# Connectors.net
KiCad netlist of a schematic drawn in Altium Designer
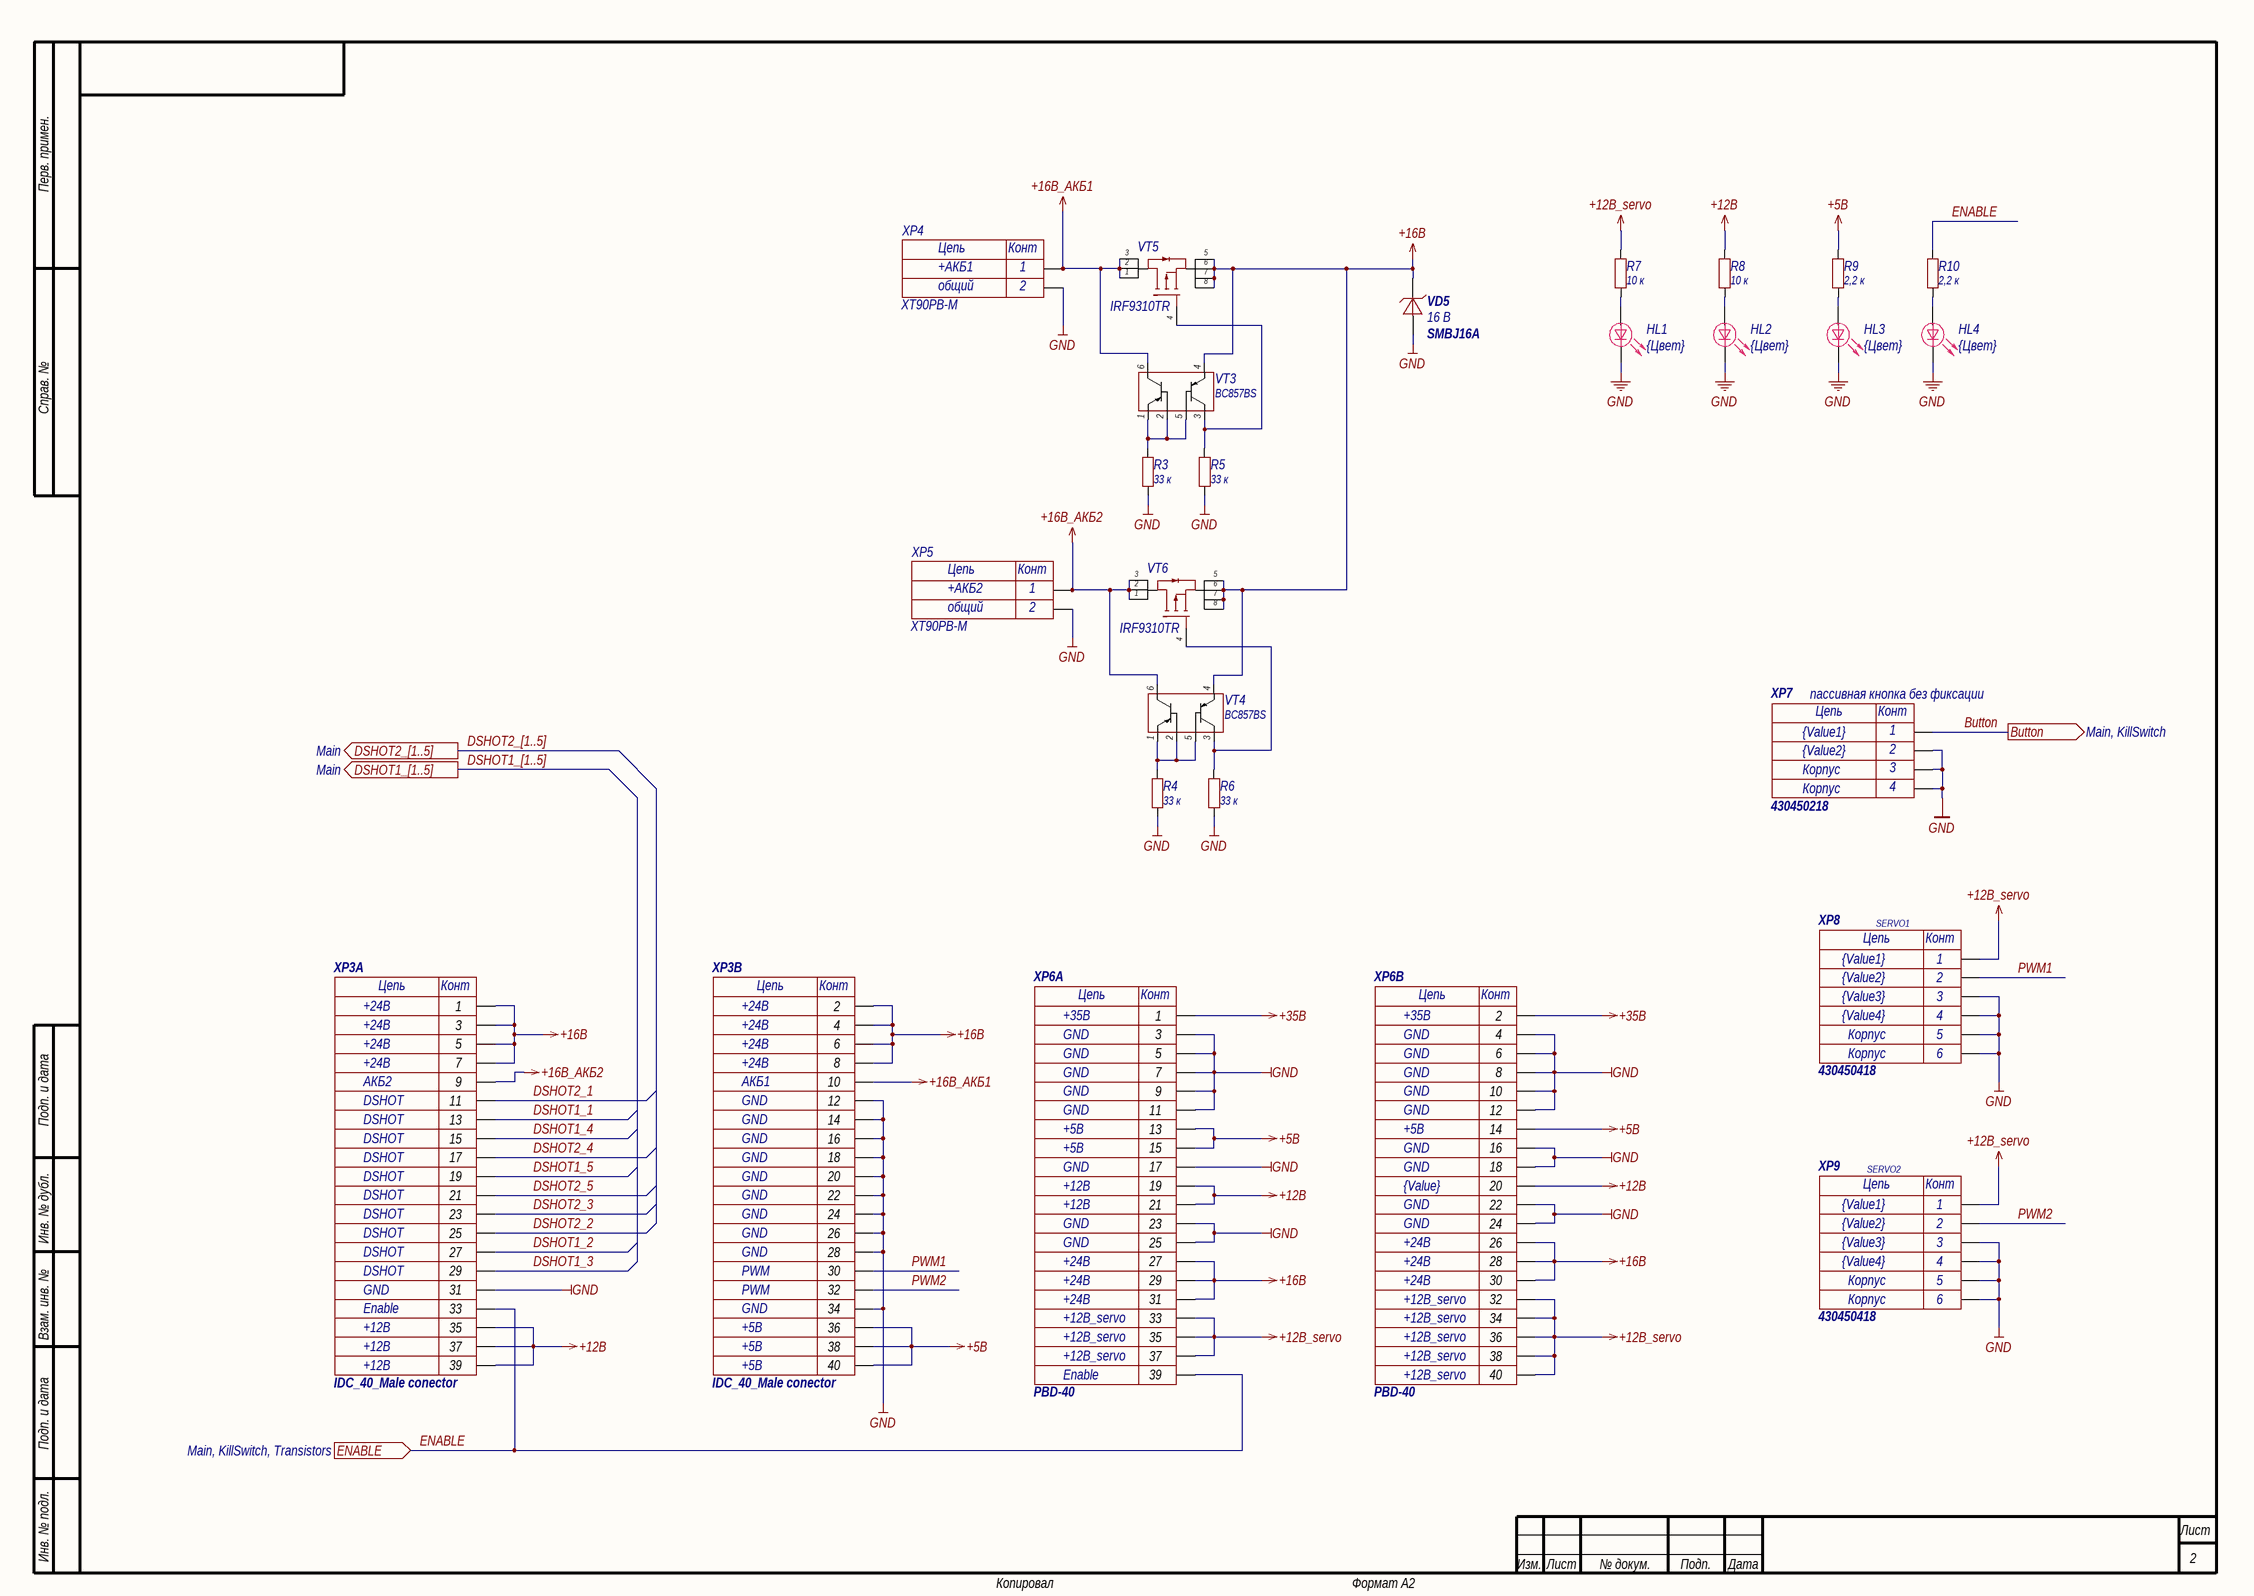
[diagram p0: Connectors.SchDoc]

(export (version "E")
  (design (tool "Eeschema 10.0.6"))
  (components
    (comp (ref "HL1")
      (value "LED")
      (footprint "0805D")
      (description "Светодиод")
      (fields (field (name "COLOR") "{Цвет}"))
      (libsource (lib "Hydrolib") (part "LED"))
    )
    (comp (ref "HL2")
      (value "LED")
      (footprint "0805D")
      (description "Светодиод")
      (fields (field (name "COLOR") "{Цвет}"))
      (libsource (lib "Hydrolib") (part "LED"))
    )
    (comp (ref "HL3")
      (value "LED")
      (footprint "0805D")
      (description "Светодиод")
      (fields (field (name "COLOR") "{Цвет}"))
      (libsource (lib "Hydrolib") (part "LED"))
    )
    (comp (ref "HL4")
      (value "LED")
      (footprint "0805D")
      (description "Светодиод")
      (fields (field (name "COLOR") "{Цвет}"))
      (libsource (lib "Hydrolib") (part "LED"))
    )
    (comp (ref "R3")
      (value "33 к")
      (footprint "0603R")
      (description "Резистор номиналом 33 кОм и точностью 1%")
      (fields (field (name "PART NUMBER") "Resistor_33k_1_0603") (field (name "TOLERANCE") "1%"))
      (libsource (lib "Hydrolib") (part "Resistor"))
    )
    (comp (ref "R4")
      (value "33 к")
      (footprint "0603R")
      (description "Резистор номиналом 33 кОм и точностью 1%")
      (fields (field (name "PART NUMBER") "Resistor_33k_1_0603") (field (name "TOLERANCE") "1%"))
      (libsource (lib "Hydrolib") (part "Resistor"))
    )
    (comp (ref "R5")
      (value "33 к")
      (footprint "0603R")
      (description "Резистор номиналом 33 кОм и точностью 1%")
      (fields (field (name "PART NUMBER") "Resistor_33k_1_0603") (field (name "TOLERANCE") "1%"))
      (libsource (lib "Hydrolib") (part "Resistor"))
    )
    (comp (ref "R6")
      (value "33 к")
      (footprint "0603R")
      (description "Резистор номиналом 33 кОм и точностью 1%")
      (fields (field (name "PART NUMBER") "Resistor_33k_1_0603") (field (name "TOLERANCE") "1%"))
      (libsource (lib "Hydrolib") (part "Resistor"))
    )
    (comp (ref "R7")
      (value "10 к")
      (footprint "0603R")
      (description "Резистор номиналом 10 кОм и точностью 1%")
      (fields (field (name "PART NUMBER") "Resistor_10k_1_0603") (field (name "TOLERANCE") "1%"))
      (libsource (lib "Hydrolib") (part "Resistor"))
    )
    (comp (ref "R8")
      (value "10 к")
      (footprint "0603R")
      (description "Резистор номиналом 10 кОм и точностью 1%")
      (fields (field (name "PART NUMBER") "Resistor_10k_1_0603") (field (name "TOLERANCE") "1%"))
      (libsource (lib "Hydrolib") (part "Resistor"))
    )
    (comp (ref "R9")
      (value "2,2 к")
      (footprint "0603R")
      (description "Резистор номиналом 2,2 кОм и точностью 1%")
      (fields (field (name "PART NUMBER") "Resistor_2.2k_1_0603") (field (name "TOLERANCE") "1%"))
      (libsource (lib "Hydrolib") (part "Resistor"))
    )
    (comp (ref "R10")
      (value "2,2 к")
      (footprint "0603R")
      (description "Резистор номиналом 2,2 кОм и точностью 1%")
      (fields (field (name "PART NUMBER") "Resistor_2.2k_1_0603") (field (name "TOLERANCE") "1%"))
      (libsource (lib "Hydrolib") (part "Resistor"))
    )
    (comp (ref "VD5")
      (value "SMBJ16A")
      (footprint "SMB")
      (description "Защитный диод на 16 В, рассеиваемая мощность 600 Вт")
      (fields (field (name "ALTIUM_VALUE") "16 В") (field (name "АВТОР") "glebmih"))
      (libsource (lib "Hydrolib") (part "TVS_1_1dir"))
    )
    (comp (ref "VT3")
      (value "BC857BS")
      (footprint "SOT-363_35um")
      (description "Сборка из биполярных транзисторов, 2 pnp, 45 В,  0.1А")
      (fields (field (name "АВТОР") "glebmih"))
      (libsource (lib "Hydrolib") (part "2pnp"))
    )
    (comp (ref "VT4")
      (value "BC857BS")
      (footprint "SOT-363_35um")
      (description "Сборка из биполярных транзисторов, 2 pnp, 45 В,  0.1А")
      (fields (field (name "АВТОР") "glebmih"))
      (libsource (lib "Hydrolib") (part "2pnp"))
    )
    (comp (ref "VT5")
      (value "IRF9310TR")
      (footprint "SOIC-8")
      (description "P-канальный MOSFET, 30 В, 20 А")
      (fields (field (name "АВТОР") "glebmih"))
      (libsource (lib "Hydrolib") (part "MOSFET_P-channel_8pin"))
    )
    (comp (ref "VT6")
      (value "IRF9310TR")
      (footprint "SOIC-8")
      (description "P-канальный MOSFET, 30 В, 20 А")
      (fields (field (name "АВТОР") "glebmih"))
      (libsource (lib "Hydrolib") (part "MOSFET_P-channel_8pin"))
    )
    (comp (ref "XP3")
      (value "IDC_40_Male conector")
      (footprint "IDC_40_Male conector")
      (description "IDC 40-пиновый разъём прямая вилка")
      (fields
        (field (name "VALUE17") "Enable")
        (field (name "VALUE20") "+12В")
        (field (name "VALUE19") "+12В")
        (field (name "VALUE18") "+12В")
        (field (name "VALUE16") "GND")
        (field (name "VALUE15") "DSHOT")
        (field (name "VALUE14") "DSHOT")
        (field (name "VALUE13") "DSHOT")
        (field (name "VALUE12") "DSHOT")
        (field (name "VALUE11") "DSHOT")
        (field (name "VALUE10") "DSHOT")
        (field (name "VALUE9") "DSHOT")
        (field (name "VALUE8") "DSHOT")
        (field (name "VALUE7") "DSHOT")
        (field (name "VALUE6") "DSHOT")
        (field (name "VALUE5") "АКБ2")
        (field (name "VALUE1") "+24В")
        (field (name "VALUE1_1") "+24В")
        (field (name "VALUE1_2") "+24В")
        (field (name "VALUE1_3") "+24В")
        (field (name "VALUE4") "+24В")
        (field (name "VALUE3") "+24В")
        (field (name "VALUE2") "+24В")
      )
      (libsource (lib "Hydrolib") (part "Conn_40pin_double"))
    )
    (comp (ref "XP4")
      (value "XT90PB-M")
      (footprint "XT90PB-M")
      (description "90 А (60 продолжительно), 2 контакта, прямой отец")
      (fields (field (name "VALUE2") "общий") (field (name "VALUE1") "+АКБ1"))
      (libsource (lib "Hydrolib") (part "Polar_Conn"))
    )
    (comp (ref "XP5")
      (value "XT90PB-M")
      (footprint "XT90PB-M")
      (description "90 А (60 продолжительно), 2 контакта, прямой отец")
      (fields (field (name "VALUE2") "общий") (field (name "VALUE1") "+АКБ2"))
      (libsource (lib "Hydrolib") (part "Polar_Conn"))
    )
    (comp (ref "XP6")
      (value "PBD-40")
      (footprint "DCDC_SAUVC26:DCDC_SAUVC26")
      (description "Плата DCDC преобрахователей")
      (fields
        (field (name "VALUE17") "+12В_servo")
        (field (name "VALUE20") "Enable")
        (field (name "VALUE19") "+12В_servo")
        (field (name "VALUE18") "+12В_servo")
        (field (name "VALUE16") "+24В")
        (field (name "VALUE15") "+24В")
        (field (name "VALUE14") "+24В")
        (field (name "VALUE13") "GND")
        (field (name "VALUE12") "GND")
        (field (name "VALUE11") "+12В")
        (field (name "VALUE10") "+12В")
        (field (name "VALUE9") "GND")
        (field (name "VALUE8") "+5В")
        (field (name "VALUE7") "+5В")
        (field (name "VALUE6") "GND")
        (field (name "VALUE5") "GND")
        (field (name "VALUE4") "GND")
        (field (name "VALUE3") "GND")
        (field (name "VALUE2") "GND")
        (field (name "VALUE1") "+35В")
      )
      (libsource (lib "DCDC_SAUVC26") (part "DCDC_SAUVC26"))
    )
    (comp (ref "XP7")
      (value "430450218")
      (footprint "Molex_430450218")
      (fields
        (field (name "VALUE3") "Корпус")
        (field (name "VALUE2") "{Value2}")
        (field (name "VALUE4") "Корпус")
        (field (name "VALUE1") "{Value1}")
        (field (name "PART NUMBER") "Molex_430450218")
      )
      (libsource (lib "Hydrolib") (part "Molex_430450218"))
    )
    (comp (ref "XP8")
      (value "430450418")
      (footprint "MOLEX_430450418")
      (description "Разъем типа провод-плата, 3 мм, 4 контакт(-ов), Штыревой Разъем, для поверностного монтажа")
      (fields
        (field (name "VALUE1") "{Value1}")
        (field (name "VALUE2") "{Value2}")
        (field (name "VALUE3") "{Value3}")
        (field (name "VALUE4") "{Value4}")
        (field (name "PART NUMBER") "Molex_430450418")
      )
      (libsource (lib "Hydrolib") (part "Molex_430450415"))
    )
    (comp (ref "XP9")
      (value "430450418")
      (footprint "MOLEX_430450418")
      (description "Разъем типа провод-плата, 3 мм, 4 контакт(-ов), Штыревой Разъем, для поверностного монтажа")
      (fields
        (field (name "VALUE1") "{Value1}")
        (field (name "VALUE2") "{Value2}")
        (field (name "VALUE3") "{Value3}")
        (field (name "VALUE4") "{Value4}")
        (field (name "PART NUMBER") "Molex_430450418")
      )
      (libsource (lib "Hydrolib") (part "Molex_430450415"))
    )
  )
  (nets
    (net (code "1") (name "+5В") (class "Default")
      (node (ref "R9") (pin "2") (pinfunction "2_2") (pintype "passive"))
      (node (ref "XP3") (pin "36") (pinfunction "36_36") (pintype "passive"))
      (node (ref "XP3") (pin "38") (pinfunction "38_38") (pintype "passive"))
      (node (ref "XP3") (pin "40") (pinfunction "40_40") (pintype "passive"))
      (node (ref "XP6") (pin "13") (pinfunction "13_13") (pintype "passive"))
      (node (ref "XP6") (pin "14") (pinfunction "14_14") (pintype "passive"))
      (node (ref "XP6") (pin "15") (pinfunction "15_15") (pintype "passive"))
    )
    (net (code "2") (name "+12В") (class "Default")
      (node (ref "R8") (pin "2") (pinfunction "2_2") (pintype "passive"))
      (node (ref "XP3") (pin "35") (pinfunction "35_35") (pintype "passive"))
      (node (ref "XP3") (pin "37") (pinfunction "37_37") (pintype "passive"))
      (node (ref "XP3") (pin "39") (pinfunction "39_39") (pintype "passive"))
      (node (ref "XP6") (pin "19") (pinfunction "19_19") (pintype "passive"))
      (node (ref "XP6") (pin "20") (pinfunction "20_20") (pintype "passive"))
      (node (ref "XP6") (pin "21") (pinfunction "21_21") (pintype "passive"))
    )
    (net (code "3") (name "+12В_servo") (class "Default")
      (node (ref "R7") (pin "2") (pinfunction "2_2") (pintype "passive"))
      (node (ref "XP6") (pin "32") (pinfunction "32_32") (pintype "passive"))
      (node (ref "XP6") (pin "33") (pinfunction "33_33") (pintype "passive"))
      (node (ref "XP6") (pin "34") (pinfunction "34_34") (pintype "passive"))
      (node (ref "XP6") (pin "35") (pinfunction "35_35") (pintype "passive"))
      (node (ref "XP6") (pin "36") (pinfunction "36_36") (pintype "passive"))
      (node (ref "XP6") (pin "37") (pinfunction "37_37") (pintype "passive"))
      (node (ref "XP6") (pin "38") (pinfunction "38_38") (pintype "passive"))
      (node (ref "XP6") (pin "40") (pinfunction "40_40") (pintype "passive"))
      (node (ref "XP8") (pin "1") (pinfunction "1_1") (pintype "passive"))
      (node (ref "XP9") (pin "1") (pinfunction "1_1") (pintype "passive"))
    )
    (net (code "4") (name "+16В") (class "Default")
      (node (ref "VD5") (pin "2") (pinfunction "2_2") (pintype "passive"))
      (node (ref "VT3") (pin "4") (pinfunction "4_4") (pintype "passive"))
      (node (ref "VT4") (pin "4") (pinfunction "4_4") (pintype "passive"))
      (node (ref "VT5") (pin "5") (pinfunction "5_5") (pintype "passive"))
      (node (ref "VT5") (pin "6") (pinfunction "6_6") (pintype "passive"))
      (node (ref "VT5") (pin "7") (pinfunction "7_7") (pintype "passive"))
      (node (ref "VT5") (pin "8") (pinfunction "8_8") (pintype "passive"))
      (node (ref "VT6") (pin "5") (pinfunction "5_5") (pintype "passive"))
      (node (ref "VT6") (pin "6") (pinfunction "6_6") (pintype "passive"))
      (node (ref "VT6") (pin "7") (pinfunction "7_7") (pintype "passive"))
      (node (ref "VT6") (pin "8") (pinfunction "8_8") (pintype "passive"))
      (node (ref "XP3") (pin "1") (pinfunction "1_1") (pintype "passive"))
      (node (ref "XP3") (pin "2") (pinfunction "2_2") (pintype "passive"))
      (node (ref "XP3") (pin "3") (pinfunction "3_3") (pintype "passive"))
      (node (ref "XP3") (pin "4") (pinfunction "4_4") (pintype "passive"))
      (node (ref "XP3") (pin "5") (pinfunction "5_5") (pintype "passive"))
      (node (ref "XP3") (pin "6") (pinfunction "6_6") (pintype "passive"))
      (node (ref "XP3") (pin "7") (pinfunction "7_7") (pintype "passive"))
      (node (ref "XP3") (pin "8") (pinfunction "8_8") (pintype "passive"))
      (node (ref "XP6") (pin "26") (pinfunction "26_26") (pintype "passive"))
      (node (ref "XP6") (pin "27") (pinfunction "27_27") (pintype "passive"))
      (node (ref "XP6") (pin "28") (pinfunction "28_28") (pintype "passive"))
      (node (ref "XP6") (pin "29") (pinfunction "29_29") (pintype "passive"))
      (node (ref "XP6") (pin "30") (pinfunction "30_30") (pintype "passive"))
      (node (ref "XP6") (pin "31") (pinfunction "31_31") (pintype "passive"))
    )
    (net (code "5") (name "+16В_АКБ1") (class "Default")
      (node (ref "VT3") (pin "6") (pinfunction "6_6") (pintype "passive"))
      (node (ref "VT5") (pin "1") (pinfunction "1_1") (pintype "passive"))
      (node (ref "VT5") (pin "2") (pinfunction "2_2") (pintype "passive"))
      (node (ref "VT5") (pin "3") (pinfunction "3_3") (pintype "passive"))
      (node (ref "XP3") (pin "10") (pinfunction "10_10") (pintype "passive"))
      (node (ref "XP4") (pin "P") (pinfunction "P_P") (pintype "passive"))
    )
    (net (code "6") (name "+16В_АКБ2") (class "Default")
      (node (ref "VT4") (pin "6") (pinfunction "6_6") (pintype "passive"))
      (node (ref "VT6") (pin "1") (pinfunction "1_1") (pintype "passive"))
      (node (ref "VT6") (pin "2") (pinfunction "2_2") (pintype "passive"))
      (node (ref "VT6") (pin "3") (pinfunction "3_3") (pintype "passive"))
      (node (ref "XP3") (pin "9") (pinfunction "9_9") (pintype "passive"))
      (node (ref "XP5") (pin "P") (pinfunction "P_P") (pintype "passive"))
    )
    (net (code "7") (name "+35В") (class "Default")
      (node (ref "XP6") (pin "1") (pinfunction "1_1") (pintype "passive"))
      (node (ref "XP6") (pin "2") (pinfunction "2_2") (pintype "passive"))
    )
    (net (code "8") (name "/Button") (class "Default")
      (node (ref "XP7") (pin "1") (pinfunction "1_1") (pintype "passive"))
    )
    (net (code "9") (name "/DSHOT1_1") (class "Default")
      (node (ref "XP3") (pin "13") (pinfunction "13_13") (pintype "passive"))
    )
    (net (code "10") (name "/DSHOT1_2") (class "Default")
      (node (ref "XP3") (pin "27") (pinfunction "27_27") (pintype "passive"))
    )
    (net (code "11") (name "/DSHOT1_3") (class "Default")
      (node (ref "XP3") (pin "29") (pinfunction "29_29") (pintype "passive"))
    )
    (net (code "12") (name "/DSHOT1_4") (class "Default")
      (node (ref "XP3") (pin "15") (pinfunction "15_15") (pintype "passive"))
    )
    (net (code "13") (name "/DSHOT1_5") (class "Default")
      (node (ref "XP3") (pin "19") (pinfunction "19_19") (pintype "passive"))
    )
    (net (code "15") (name "/DSHOT2_1") (class "Default")
      (node (ref "XP3") (pin "11") (pinfunction "11_11") (pintype "passive"))
    )
    (net (code "16") (name "/DSHOT2_2") (class "Default")
      (node (ref "XP3") (pin "25") (pinfunction "25_25") (pintype "passive"))
    )
    (net (code "17") (name "/DSHOT2_3") (class "Default")
      (node (ref "XP3") (pin "23") (pinfunction "23_23") (pintype "passive"))
    )
    (net (code "18") (name "/DSHOT2_4") (class "Default")
      (node (ref "XP3") (pin "17") (pinfunction "17_17") (pintype "passive"))
    )
    (net (code "19") (name "/DSHOT2_5") (class "Default")
      (node (ref "XP3") (pin "21") (pinfunction "21_21") (pintype "passive"))
    )
    (net (code "21") (name "/ENABLE") (class "Default")
      (node (ref "R10") (pin "2") (pinfunction "2_2") (pintype "passive"))
      (node (ref "XP3") (pin "33") (pinfunction "33_33") (pintype "passive"))
      (node (ref "XP6") (pin "39") (pinfunction "39_39") (pintype "passive"))
    )
    (net (code "22") (name "/PWM1") (class "Default")
      (node (ref "XP3") (pin "30") (pinfunction "30_30") (pintype "passive"))
      (node (ref "XP8") (pin "2") (pinfunction "2_2") (pintype "passive"))
    )
    (net (code "23") (name "/PWM2") (class "Default")
      (node (ref "XP3") (pin "32") (pinfunction "32_32") (pintype "passive"))
      (node (ref "XP9") (pin "2") (pinfunction "2_2") (pintype "passive"))
    )
    (net (code "24") (name "GND") (class "Default")
      (node (ref "HL1") (pin "2") (pinfunction "2_2") (pintype "passive"))
      (node (ref "HL2") (pin "2") (pinfunction "2_2") (pintype "passive"))
      (node (ref "HL3") (pin "2") (pinfunction "2_2") (pintype "passive"))
      (node (ref "HL4") (pin "2") (pinfunction "2_2") (pintype "passive"))
      (node (ref "R3") (pin "1") (pinfunction "1_1") (pintype "passive"))
      (node (ref "R4") (pin "1") (pinfunction "1_1") (pintype "passive"))
      (node (ref "R5") (pin "1") (pinfunction "1_1") (pintype "passive"))
      (node (ref "R6") (pin "1") (pinfunction "1_1") (pintype "passive"))
      (node (ref "VD5") (pin "1") (pinfunction "1_1") (pintype "passive"))
      (node (ref "XP3") (pin "12") (pinfunction "12_12") (pintype "passive"))
      (node (ref "XP3") (pin "14") (pinfunction "14_14") (pintype "passive"))
      (node (ref "XP3") (pin "16") (pinfunction "16_16") (pintype "passive"))
      (node (ref "XP3") (pin "18") (pinfunction "18_18") (pintype "passive"))
      (node (ref "XP3") (pin "20") (pinfunction "20_20") (pintype "passive"))
      (node (ref "XP3") (pin "22") (pinfunction "22_22") (pintype "passive"))
      (node (ref "XP3") (pin "24") (pinfunction "24_24") (pintype "passive"))
      (node (ref "XP3") (pin "26") (pinfunction "26_26") (pintype "passive"))
      (node (ref "XP3") (pin "28") (pinfunction "28_28") (pintype "passive"))
      (node (ref "XP3") (pin "31") (pinfunction "31_31") (pintype "passive"))
      (node (ref "XP3") (pin "34") (pinfunction "34_34") (pintype "passive"))
      (node (ref "XP4") (pin "N") (pinfunction "N_N") (pintype "passive"))
      (node (ref "XP5") (pin "N") (pinfunction "N_N") (pintype "passive"))
      (node (ref "XP6") (pin "10") (pinfunction "10_10") (pintype "passive"))
      (node (ref "XP6") (pin "11") (pinfunction "11_11") (pintype "passive"))
      (node (ref "XP6") (pin "12") (pinfunction "12_12") (pintype "passive"))
      (node (ref "XP6") (pin "16") (pinfunction "16_16") (pintype "passive"))
      (node (ref "XP6") (pin "17") (pinfunction "17_17") (pintype "passive"))
      (node (ref "XP6") (pin "18") (pinfunction "18_18") (pintype "passive"))
      (node (ref "XP6") (pin "22") (pinfunction "22_22") (pintype "passive"))
      (node (ref "XP6") (pin "23") (pinfunction "23_23") (pintype "passive"))
      (node (ref "XP6") (pin "24") (pinfunction "24_24") (pintype "passive"))
      (node (ref "XP6") (pin "25") (pinfunction "25_25") (pintype "passive"))
      (node (ref "XP6") (pin "3") (pinfunction "3_3") (pintype "passive"))
      (node (ref "XP6") (pin "4") (pinfunction "4_4") (pintype "passive"))
      (node (ref "XP6") (pin "5") (pinfunction "5_5") (pintype "passive"))
      (node (ref "XP6") (pin "6") (pinfunction "6_6") (pintype "passive"))
      (node (ref "XP6") (pin "7") (pinfunction "7_7") (pintype "passive"))
      (node (ref "XP6") (pin "8") (pinfunction "8_8") (pintype "passive"))
      (node (ref "XP6") (pin "9") (pinfunction "9_9") (pintype "passive"))
      (node (ref "XP7") (pin "0") (pinfunction "0_0") (pintype "passive"))
      (node (ref "XP7") (pin "2") (pinfunction "2_2") (pintype "passive"))
      (node (ref "XP8") (pin "0") (pinfunction "0_0") (pintype "passive"))
      (node (ref "XP8") (pin "3") (pinfunction "3_3") (pintype "passive"))
      (node (ref "XP8") (pin "4") (pinfunction "4_4") (pintype "passive"))
      (node (ref "XP9") (pin "0") (pinfunction "0_0") (pintype "passive"))
      (node (ref "XP9") (pin "3") (pinfunction "3_3") (pintype "passive"))
      (node (ref "XP9") (pin "4") (pinfunction "4_4") (pintype "passive"))
    )
    (net (code "25") (name "Net-(HL1-Pad1)") (class "Default")
      (node (ref "HL1") (pin "1") (pinfunction "1_1") (pintype "passive"))
      (node (ref "R7") (pin "1") (pinfunction "1_1") (pintype "passive"))
    )
    (net (code "26") (name "Net-(HL2-Pad1)") (class "Default")
      (node (ref "HL2") (pin "1") (pinfunction "1_1") (pintype "passive"))
      (node (ref "R8") (pin "1") (pinfunction "1_1") (pintype "passive"))
    )
    (net (code "27") (name "Net-(HL3-Pad1)") (class "Default")
      (node (ref "HL3") (pin "1") (pinfunction "1_1") (pintype "passive"))
      (node (ref "R9") (pin "1") (pinfunction "1_1") (pintype "passive"))
    )
    (net (code "28") (name "Net-(HL4-Pad1)") (class "Default")
      (node (ref "HL4") (pin "1") (pinfunction "1_1") (pintype "passive"))
      (node (ref "R10") (pin "1") (pinfunction "1_1") (pintype "passive"))
    )
    (net (code "29") (name "Net-(R3-Pad2)") (class "Default")
      (node (ref "R3") (pin "2") (pinfunction "2_2") (pintype "passive"))
      (node (ref "VT3") (pin "1") (pinfunction "1_1") (pintype "passive"))
      (node (ref "VT3") (pin "2") (pinfunction "2_2") (pintype "passive"))
      (node (ref "VT3") (pin "5") (pinfunction "5_5") (pintype "passive"))
    )
    (net (code "30") (name "Net-(R4-Pad2)") (class "Default")
      (node (ref "R4") (pin "2") (pinfunction "2_2") (pintype "passive"))
      (node (ref "VT4") (pin "1") (pinfunction "1_1") (pintype "passive"))
      (node (ref "VT4") (pin "2") (pinfunction "2_2") (pintype "passive"))
      (node (ref "VT4") (pin "5") (pinfunction "5_5") (pintype "passive"))
    )
    (net (code "31") (name "Net-(R5-Pad2)") (class "Default")
      (node (ref "R5") (pin "2") (pinfunction "2_2") (pintype "passive"))
      (node (ref "VT3") (pin "3") (pinfunction "3_3") (pintype "passive"))
      (node (ref "VT5") (pin "4") (pinfunction "4_4") (pintype "passive"))
    )
    (net (code "32") (name "Net-(R6-Pad2)") (class "Default")
      (node (ref "R6") (pin "2") (pinfunction "2_2") (pintype "passive"))
      (node (ref "VT4") (pin "3") (pinfunction "3_3") (pintype "passive"))
      (node (ref "VT6") (pin "4") (pinfunction "4_4") (pintype "passive"))
    )
  )
)
